# msmobilshield.net
KiCad netlist of a schematic drawn in EAGLE
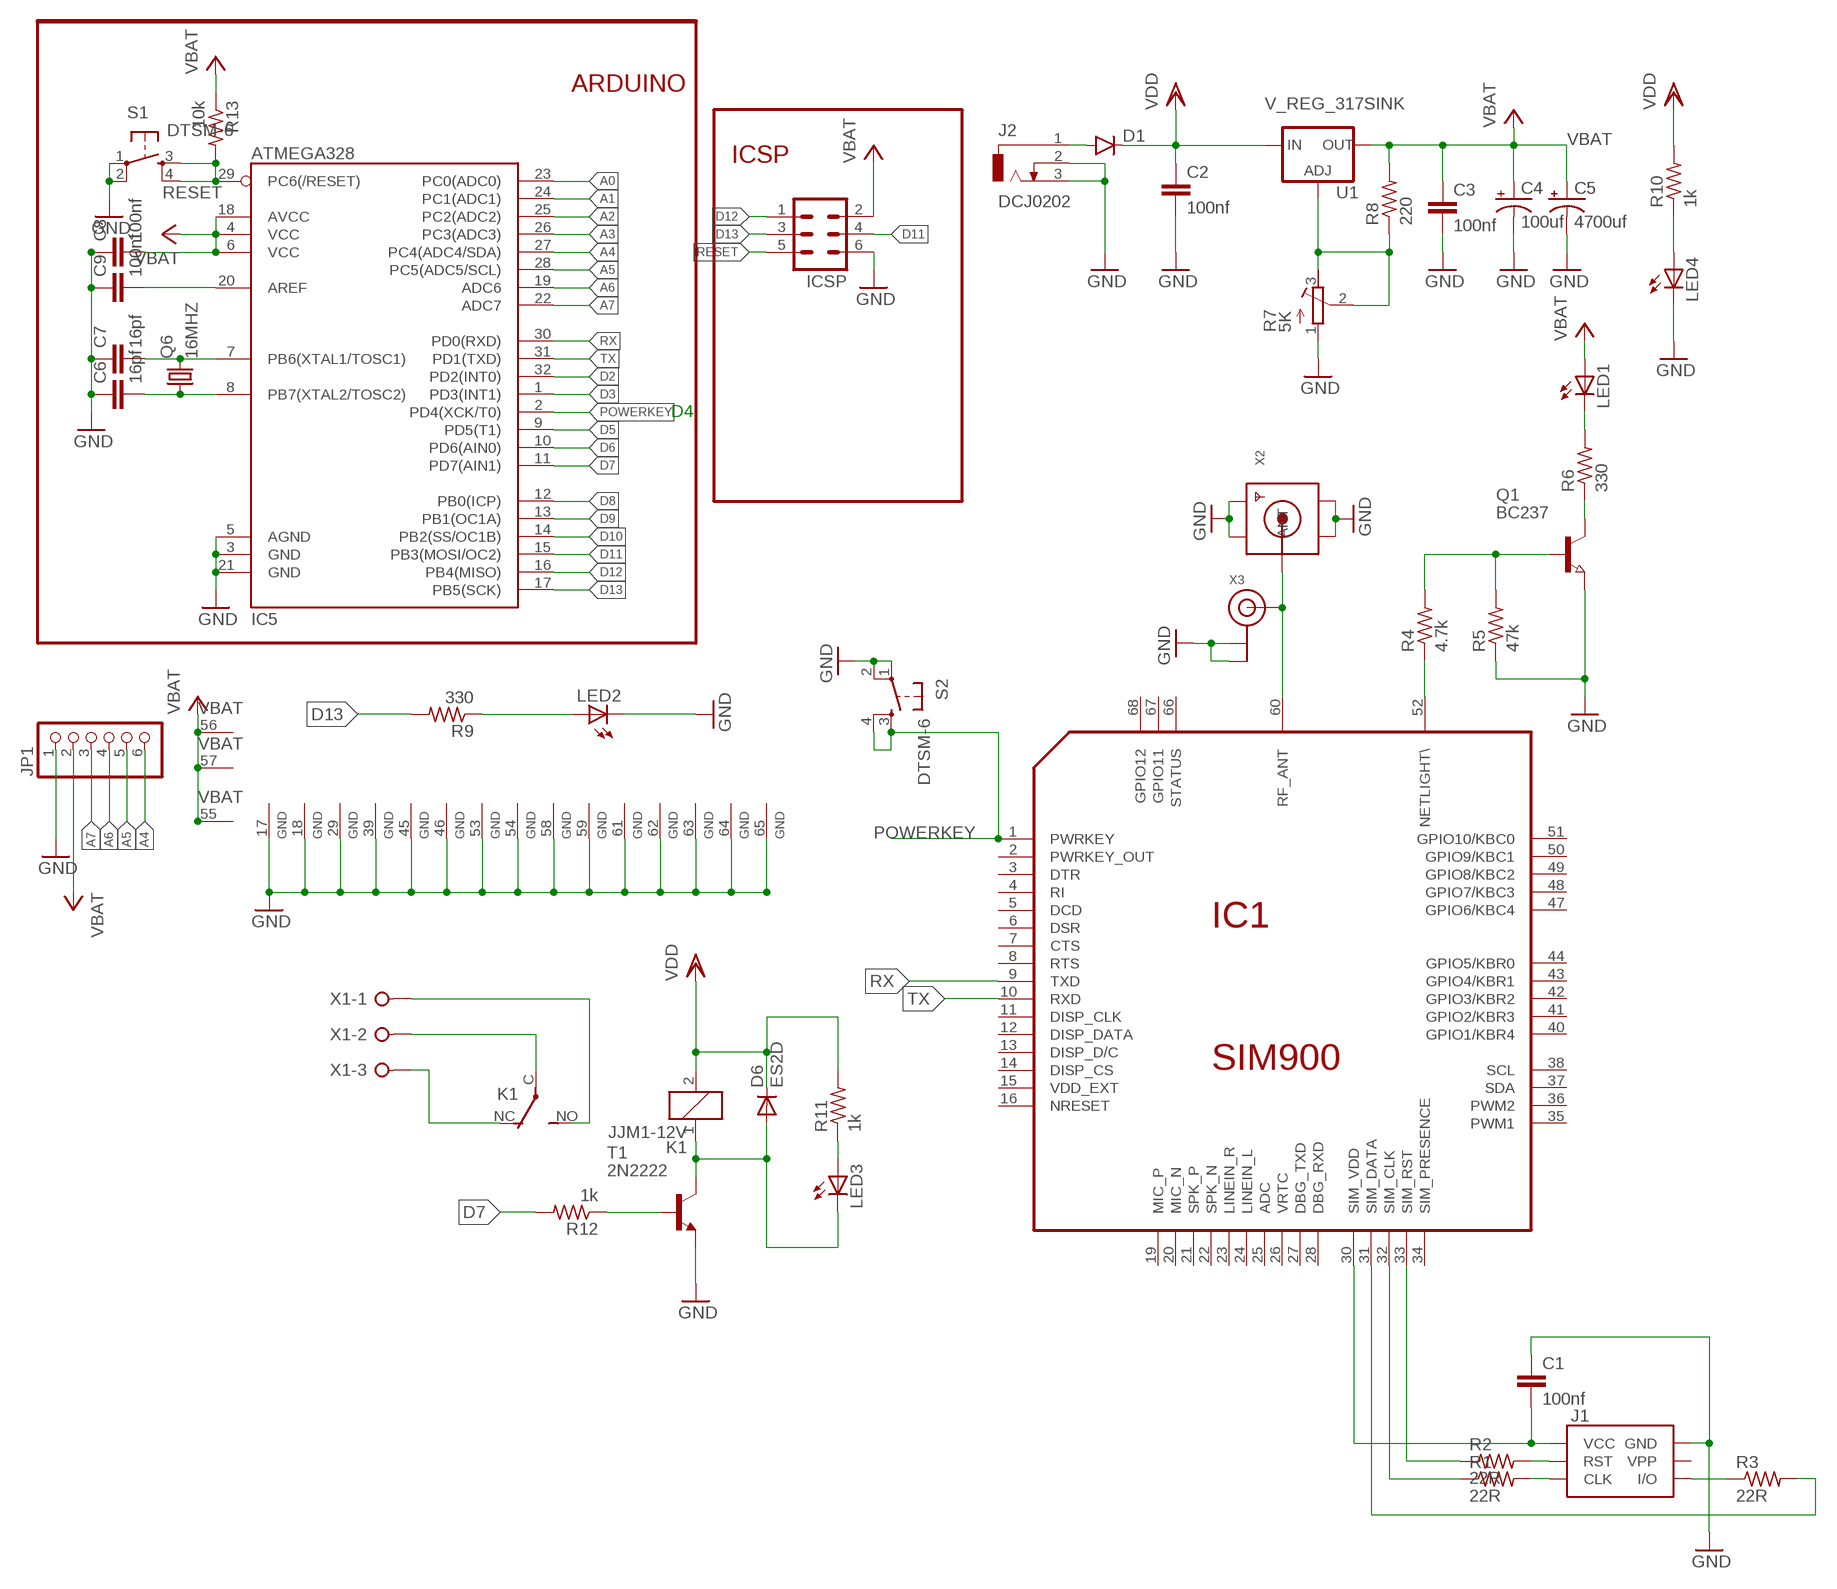
[diagram p0: schematic, sheet 1]

(export (version "E")
  (design (tool "Eeschema 10.0.6"))
  (components
    (comp (ref "C1")
      (value "100nf")
      (footprint "eagle-import:C0805")
      (libsource (lib "eagle-import") (part "C-EUC0805"))
    )
    (comp (ref "C2")
      (value "100nf")
      (footprint "eagle-import:C0805")
      (libsource (lib "eagle-import") (part "C-EUC0805"))
    )
    (comp (ref "C3")
      (value "100nf")
      (footprint "eagle-import:C0805")
      (libsource (lib "eagle-import") (part "C-EUC0805"))
    )
    (comp (ref "C4")
      (value "100uf")
      (footprint "eagle-import:CPOL-RADIAL-100UF-25V")
      (libsource (lib "eagle-import") (part "100UF-25V-20%(PTH)"))
    )
    (comp (ref "C5")
      (value "4700uf")
      (footprint "eagle-import:CPOL-RADIAL-1000UF-25V")
      (libsource (lib "eagle-import") (part "1000UF-25V(PTH)"))
    )
    (comp (ref "C6")
      (value "16pf")
      (footprint "eagle-import:C0805")
      (libsource (lib "eagle-import") (part "C-EUC0805"))
    )
    (comp (ref "C7")
      (value "16pf")
      (footprint "eagle-import:C0805")
      (libsource (lib "eagle-import") (part "C-EUC0805"))
    )
    (comp (ref "C8")
      (value "100nf")
      (footprint "eagle-import:C0805")
      (libsource (lib "eagle-import") (part "C-EUC0805"))
    )
    (comp (ref "C9")
      (value "100nf")
      (footprint "eagle-import:C0805")
      (libsource (lib "eagle-import") (part "C-EUC0805"))
    )
    (comp (ref "D1")
      (value "DIODESMA")
      (footprint "eagle-import:SMA-DIODE")
      (libsource (lib "eagle-import") (part "DIODESMA"))
    )
    (comp (ref "D6")
      (value "ES2D")
      (footprint "eagle-import:SMB")
      (libsource (lib "eagle-import") (part "ES2D"))
    )
    (comp (ref "IC1")
      (value "SIM900")
      (footprint "eagle-import:SIM900")
      (libsource (lib "eagle-import") (part "SIM900"))
    )
    (comp (ref "IC5")
      (value "ATMEGA328")
      (footprint "eagle-import:TQFP32-08")
      (libsource (lib "eagle-import") (part "ATMEGA168"))
    )
    (comp (ref "ICSP")
      (value "ML6")
      (footprint "eagle-import:ML6")
      (libsource (lib "eagle-import") (part "ML6"))
    )
    (comp (ref "J1")
      (value "SIMHOLDERSIM")
      (footprint "eagle-import:SIMHOLDER")
      (libsource (lib "eagle-import") (part "SIMHOLDERSIM"))
    )
    (comp (ref "J2")
      (value "DCJ0202")
      (footprint "eagle-import:DCJ0202")
      (libsource (lib "eagle-import") (part "DCJ0202"))
    )
    (comp (ref "JP1")
      (value "PINHD-1X6")
      (footprint "eagle-import:1X06")
      (libsource (lib "eagle-import") (part "PINHD-1X6"))
    )
    (comp (ref "K1")
      (value "JJM1-12V")
      (footprint "eagle-import:JJM1C")
      (fields (field (name "MF") "AROMAT/ MATSUSHITA"))
      (libsource (lib "eagle-import") (part "JJM1-12V"))
    )
    (comp (ref "LED1")
      (value "LEDCHIPLED_0805")
      (footprint "eagle-import:CHIPLED_0805")
      (libsource (lib "eagle-import") (part "LEDCHIPLED_0805"))
    )
    (comp (ref "LED2")
      (value "LEDCHIPLED_0805")
      (footprint "eagle-import:CHIPLED_0805")
      (libsource (lib "eagle-import") (part "LEDCHIPLED_0805"))
    )
    (comp (ref "LED3")
      (value "LEDCHIPLED_0805")
      (footprint "eagle-import:CHIPLED_0805")
      (libsource (lib "eagle-import") (part "LEDCHIPLED_0805"))
    )
    (comp (ref "LED4")
      (value "LEDCHIPLED_0805")
      (footprint "eagle-import:CHIPLED_0805")
      (libsource (lib "eagle-import") (part "LEDCHIPLED_0805"))
    )
    (comp (ref "Q1")
      (value "BC237")
      (footprint "eagle-import:SOT23")
      (libsource (lib "eagle-import") (part "NPN-TRANSISTOR_SOT23"))
    )
    (comp (ref "Q6")
      (value "16MHZ")
      (footprint "eagle-import:HC49_S")
      (libsource (lib "eagle-import") (part "CRYSTALHC49S"))
    )
    (comp (ref "R1")
      (value "22R")
      (footprint "eagle-import:R0805")
      (libsource (lib "eagle-import") (part "R-US_R0805"))
    )
    (comp (ref "R2")
      (value "22R")
      (footprint "eagle-import:R0805")
      (libsource (lib "eagle-import") (part "R-US_R0805"))
    )
    (comp (ref "R3")
      (value "22R")
      (footprint "eagle-import:R0805")
      (libsource (lib "eagle-import") (part "R-US_R0805"))
    )
    (comp (ref "R4")
      (value "4.7k")
      (footprint "eagle-import:R0805")
      (libsource (lib "eagle-import") (part "R-US_R0805"))
    )
    (comp (ref "R5")
      (value "47k")
      (footprint "eagle-import:R0805")
      (libsource (lib "eagle-import") (part "R-US_R0805"))
    )
    (comp (ref "R6")
      (value "330")
      (footprint "eagle-import:R0805")
      (libsource (lib "eagle-import") (part "R-US_R0805"))
    )
    (comp (ref "R7")
      (value "5K")
      (footprint "eagle-import:RTRIM3103")
      (libsource (lib "eagle-import") (part "R-TRIMM3103"))
    )
    (comp (ref "R8")
      (value "220")
      (footprint "eagle-import:R0805")
      (libsource (lib "eagle-import") (part "R-US_R0805"))
    )
    (comp (ref "R9")
      (value "330")
      (footprint "eagle-import:R0805")
      (libsource (lib "eagle-import") (part "R-US_R0805"))
    )
    (comp (ref "R10")
      (value "1k")
      (footprint "eagle-import:R0805")
      (libsource (lib "eagle-import") (part "R-US_R0805"))
    )
    (comp (ref "R11")
      (value "1k")
      (footprint "eagle-import:R0805")
      (libsource (lib "eagle-import") (part "R-US_R0805"))
    )
    (comp (ref "R12")
      (value "1k")
      (footprint "eagle-import:R0805")
      (libsource (lib "eagle-import") (part "R-US_R0805"))
    )
    (comp (ref "R13")
      (value "10k")
      (footprint "eagle-import:R0805")
      (libsource (lib "eagle-import") (part "R-US_R0805"))
    )
    (comp (ref "S1")
      (value "DTSM-6")
      (footprint "eagle-import:DTSM-6")
      (libsource (lib "eagle-import") (part "DTSM-6"))
    )
    (comp (ref "S2")
      (value "DTSM-6")
      (footprint "eagle-import:DTSM-6")
      (libsource (lib "eagle-import") (part "DTSM-6"))
    )
    (comp (ref "T1")
      (value "2N2222")
      (footprint "eagle-import:SOT23-BEC")
      (libsource (lib "eagle-import") (part "-NPN-SOT23-BECMMBT2222ALT1"))
    )
    (comp (ref "U1")
      (value "V_REG_317SINK")
      (footprint "eagle-import:TO220-ADJ")
      (libsource (lib "eagle-import") (part "V_REG_317SINK"))
    )
    (comp (ref "X1")
      (value "W237-3E")
      (footprint "eagle-import:W237-3E")
      (libsource (lib "eagle-import") (part "W237-3E"))
    )
    (comp (ref "X2")
      (value "SMACONNECTOR")
      (footprint "eagle-import:SMA90_DIP")
      (libsource (lib "eagle-import") (part "SMACONNECTOR"))
    )
    (comp (ref "X3")
      (value "ANTENNA_U.FL")
      (footprint "eagle-import:U.FL")
      (libsource (lib "eagle-import") (part "ANTENNA_U.FL"))
    )
  )
  (nets
    (net (code "1") (name "A0") (class "Default")
      (node (ref "IC5") (pin "23") (pinfunction "PC0(ADC0)_23") (pintype "bidirectional"))
    )
    (net (code "2") (name "A1") (class "Default")
      (node (ref "IC5") (pin "24") (pinfunction "PC1(ADC1)_24") (pintype "bidirectional"))
    )
    (net (code "3") (name "A2") (class "Default")
      (node (ref "IC5") (pin "25") (pinfunction "PC2(ADC2)_25") (pintype "bidirectional"))
    )
    (net (code "4") (name "A3") (class "Default")
      (node (ref "IC5") (pin "26") (pinfunction "PC3(ADC3)_26") (pintype "bidirectional"))
    )
    (net (code "5") (name "A4") (class "Default")
      (node (ref "IC5") (pin "27") (pinfunction "PC4(ADC4/SDA)_27") (pintype "bidirectional"))
      (node (ref "JP1") (pin "6") (pinfunction "6_6") (pintype "passive"))
    )
    (net (code "6") (name "A5") (class "Default")
      (node (ref "IC5") (pin "28") (pinfunction "PC5(ADC5/SCL)_28") (pintype "bidirectional"))
      (node (ref "JP1") (pin "5") (pinfunction "5_5") (pintype "passive"))
    )
    (net (code "7") (name "A6") (class "Default")
      (node (ref "IC5") (pin "19") (pinfunction "ADC6_19") (pintype "bidirectional"))
      (node (ref "JP1") (pin "4") (pinfunction "4_4") (pintype "passive"))
    )
    (net (code "8") (name "A7") (class "Default")
      (node (ref "IC5") (pin "22") (pinfunction "ADC7_22") (pintype "bidirectional"))
      (node (ref "JP1") (pin "3") (pinfunction "3_3") (pintype "passive"))
    )
    (net (code "9") (name "D2") (class "Default")
      (node (ref "IC5") (pin "32") (pinfunction "PD2(INT0)_32") (pintype "bidirectional"))
    )
    (net (code "10") (name "D3") (class "Default")
      (node (ref "IC5") (pin "1") (pinfunction "PD3(INT1)_1") (pintype "bidirectional"))
    )
    (net (code "11") (name "D5") (class "Default")
      (node (ref "IC5") (pin "9") (pinfunction "PD5(T1)_9") (pintype "bidirectional"))
    )
    (net (code "12") (name "D6") (class "Default")
      (node (ref "IC5") (pin "10") (pinfunction "PD6(AIN0)_10") (pintype "bidirectional"))
    )
    (net (code "13") (name "D7") (class "Default")
      (node (ref "IC5") (pin "11") (pinfunction "PD7(AIN1)_11") (pintype "bidirectional"))
      (node (ref "R12") (pin "2") (pinfunction "2_2") (pintype "passive"))
    )
    (net (code "14") (name "D8") (class "Default")
      (node (ref "IC5") (pin "12") (pinfunction "PB0(ICP)_12") (pintype "bidirectional"))
    )
    (net (code "15") (name "D9") (class "Default")
      (node (ref "IC5") (pin "13") (pinfunction "PB1(OC1A)_13") (pintype "bidirectional"))
    )
    (net (code "16") (name "D10") (class "Default")
      (node (ref "IC5") (pin "14") (pinfunction "PB2(SS/OC1B)_14") (pintype "bidirectional"))
    )
    (net (code "17") (name "D11") (class "Default")
      (node (ref "IC5") (pin "15") (pinfunction "PB3(MOSI/OC2)_15") (pintype "bidirectional"))
      (node (ref "ICSP") (pin "4") (pinfunction "4_4") (pintype "passive"))
    )
    (net (code "18") (name "D12") (class "Default")
      (node (ref "IC5") (pin "16") (pinfunction "PB4(MISO)_16") (pintype "bidirectional"))
      (node (ref "ICSP") (pin "1") (pinfunction "1_1") (pintype "passive"))
    )
    (net (code "19") (name "D13") (class "Default")
      (node (ref "IC5") (pin "17") (pinfunction "PB5(SCK)_17") (pintype "bidirectional"))
      (node (ref "ICSP") (pin "3") (pinfunction "3_3") (pintype "passive"))
      (node (ref "R9") (pin "2") (pinfunction "2_2") (pintype "passive"))
    )
    (net (code "20") (name "GND") (class "Default")
      (node (ref "C1") (pin "1") (pinfunction "1_1") (pintype "passive"))
      (node (ref "C2") (pin "2") (pinfunction "2_2") (pintype "passive"))
      (node (ref "C3") (pin "2") (pinfunction "2_2") (pintype "passive"))
      (node (ref "C4") (pin "2") (pinfunction "-_2") (pintype "passive"))
      (node (ref "C5") (pin "-") (pinfunction "-_-") (pintype "passive"))
      (node (ref "C6") (pin "1") (pinfunction "1_1") (pintype "passive"))
      (node (ref "C7") (pin "1") (pinfunction "1_1") (pintype "passive"))
      (node (ref "C8") (pin "1") (pinfunction "1_1") (pintype "passive"))
      (node (ref "C9") (pin "1") (pinfunction "1_1") (pintype "passive"))
      (node (ref "IC1") (pin "17") (pinfunction "GND_17") (pintype "power_in"))
      (node (ref "IC1") (pin "18") (pinfunction "GND_18") (pintype "power_in"))
      (node (ref "IC1") (pin "29") (pinfunction "GND_29") (pintype "power_in"))
      (node (ref "IC1") (pin "39") (pinfunction "GND_39") (pintype "power_in"))
      (node (ref "IC1") (pin "45") (pinfunction "GND_45") (pintype "power_in"))
      (node (ref "IC1") (pin "46") (pinfunction "GND_46") (pintype "power_in"))
      (node (ref "IC1") (pin "53") (pinfunction "GND_53") (pintype "power_in"))
      (node (ref "IC1") (pin "54") (pinfunction "GND_54") (pintype "power_in"))
      (node (ref "IC1") (pin "58") (pinfunction "GND_58") (pintype "power_in"))
      (node (ref "IC1") (pin "59") (pinfunction "GND_59") (pintype "power_in"))
      (node (ref "IC1") (pin "61") (pinfunction "GND_61") (pintype "power_in"))
      (node (ref "IC1") (pin "62") (pinfunction "GND_62") (pintype "power_in"))
      (node (ref "IC1") (pin "63") (pinfunction "GND_63") (pintype "power_in"))
      (node (ref "IC1") (pin "64") (pinfunction "GND_64") (pintype "power_in"))
      (node (ref "IC1") (pin "65") (pinfunction "GND_65") (pintype "power_in"))
      (node (ref "IC5") (pin "21") (pinfunction "GND_21") (pintype "bidirectional"))
      (node (ref "IC5") (pin "3") (pinfunction "GND_3") (pintype "bidirectional"))
      (node (ref "IC5") (pin "5") (pinfunction "AGND_5") (pintype "bidirectional"))
      (node (ref "ICSP") (pin "6") (pinfunction "6_6") (pintype "passive"))
      (node (ref "J1") (pin "C5") (pinfunction "GND_C5") (pintype "power_in"))
      (node (ref "J2") (pin "2") (pinfunction "2_2") (pintype "passive"))
      (node (ref "J2") (pin "3") (pinfunction "3_3") (pintype "passive"))
      (node (ref "JP1") (pin "1") (pinfunction "1_1") (pintype "passive"))
      (node (ref "LED2") (pin "C") (pinfunction "C_C") (pintype "passive"))
      (node (ref "LED4") (pin "C") (pinfunction "C_C") (pintype "passive"))
      (node (ref "Q1") (pin "2") (pinfunction "E_2") (pintype "passive"))
      (node (ref "R5") (pin "1") (pinfunction "1_1") (pintype "passive"))
      (node (ref "R7") (pin "1") (pinfunction "A_1") (pintype "passive"))
      (node (ref "S1") (pin "1") (pinfunction "1_1") (pintype "passive"))
      (node (ref "S1") (pin "2") (pinfunction "2_2") (pintype "passive"))
      (node (ref "S2") (pin "1") (pinfunction "1_1") (pintype "passive"))
      (node (ref "S2") (pin "2") (pinfunction "2_2") (pintype "passive"))
      (node (ref "T1") (pin "E") (pinfunction "E_E") (pintype "passive"))
      (node (ref "X2") (pin "GND1") (pinfunction "GND1_GND1") (pintype "power_in"))
      (node (ref "X2") (pin "GND2") (pinfunction "GND2_GND2") (pintype "power_in"))
      (node (ref "X2") (pin "GND3") (pinfunction "GND3_GND3") (pintype "power_in"))
      (node (ref "X2") (pin "GND4") (pinfunction "GND4_GND4") (pintype "power_in"))
      (node (ref "X3") (pin "1") (pinfunction "GND_1") (pintype "passive"))
      (node (ref "X3") (pin "2") (pinfunction "GND_2") (pintype "passive"))
    )
    (net (code "21") (name "Net-(D1-PadA)") (class "Default")
      (node (ref "D1") (pin "A") (pinfunction "A_A") (pintype "passive"))
      (node (ref "J2") (pin "1") (pinfunction "1_1") (pintype "passive"))
    )
    (net (code "22") (name "Net-(D6-PadA)") (class "Default")
      (node (ref "D6") (pin "A") (pinfunction "A_A") (pintype "passive"))
      (node (ref "K1") (pin "1") (pinfunction "1_1") (pintype "passive"))
      (node (ref "LED3") (pin "C") (pinfunction "C_C") (pintype "passive"))
      (node (ref "T1") (pin "C") (pinfunction "C_C") (pintype "passive"))
    )
    (net (code "23") (name "Net-(IC1A-NETLIGHT\\)") (class "Default")
      (node (ref "IC1") (pin "52") (pinfunction "NETLIGHT\\_52") (pintype "bidirectional"))
      (node (ref "R4") (pin "1") (pinfunction "1_1") (pintype "passive"))
    )
    (net (code "24") (name "Net-(IC1A-RF_ANT)") (class "Default")
      (node (ref "IC1") (pin "60") (pinfunction "RF_ANT_60") (pintype "bidirectional"))
      (node (ref "X2") (pin "ANTENNA") (pinfunction "ANT_ANTENNA") (pintype "bidirectional"))
      (node (ref "X3") (pin "3") (pinfunction "SIGNAL_3") (pintype "passive"))
    )
    (net (code "25") (name "Net-(IC1A-SIM_CLK)") (class "Default")
      (node (ref "IC1") (pin "32") (pinfunction "SIM_CLK_32") (pintype "bidirectional"))
      (node (ref "R1") (pin "1") (pinfunction "1_1") (pintype "passive"))
    )
    (net (code "26") (name "Net-(IC1A-SIM_DATA)") (class "Default")
      (node (ref "IC1") (pin "31") (pinfunction "SIM_DATA_31") (pintype "bidirectional"))
      (node (ref "R3") (pin "2") (pinfunction "2_2") (pintype "passive"))
    )
    (net (code "27") (name "Net-(IC1A-SIM_RST)") (class "Default")
      (node (ref "IC1") (pin "33") (pinfunction "SIM_RST_33") (pintype "bidirectional"))
      (node (ref "R2") (pin "1") (pinfunction "1_1") (pintype "passive"))
    )
    (net (code "28") (name "Net-(IC1A-SIM_VDD)") (class "Default")
      (node (ref "C1") (pin "2") (pinfunction "2_2") (pintype "passive"))
      (node (ref "IC1") (pin "30") (pinfunction "SIM_VDD_30") (pintype "bidirectional"))
      (node (ref "J1") (pin "C1") (pinfunction "VCC_C1") (pintype "power_in"))
    )
    (net (code "29") (name "Net-(IC5-AREF)") (class "Default")
      (node (ref "C9") (pin "2") (pinfunction "2_2") (pintype "passive"))
      (node (ref "IC5") (pin "20") (pinfunction "AREF_20") (pintype "bidirectional"))
    )
    (net (code "30") (name "Net-(IC5-PB6(XTAL1{slash}TOSC1))") (class "Default")
      (node (ref "C7") (pin "2") (pinfunction "2_2") (pintype "passive"))
      (node (ref "IC5") (pin "7") (pinfunction "PB6(XTAL1/TOSC1)_7") (pintype "bidirectional"))
      (node (ref "Q6") (pin "2") (pinfunction "2_2") (pintype "passive"))
    )
    (net (code "31") (name "Net-(IC5-PB7(XTAL2{slash}TOSC2))") (class "Default")
      (node (ref "C6") (pin "2") (pinfunction "2_2") (pintype "passive"))
      (node (ref "IC5") (pin "8") (pinfunction "PB7(XTAL2/TOSC2)_8") (pintype "bidirectional"))
      (node (ref "Q6") (pin "1") (pinfunction "1_1") (pintype "passive"))
    )
    (net (code "32") (name "Net-(J1-CLK)") (class "Default")
      (node (ref "J1") (pin "C3") (pinfunction "CLK_C3") (pintype "input"))
      (node (ref "R1") (pin "2") (pinfunction "2_2") (pintype "passive"))
    )
    (net (code "33") (name "Net-(J1-I{slash}O)") (class "Default")
      (node (ref "J1") (pin "C7") (pinfunction "I/O_C7") (pintype "bidirectional"))
      (node (ref "R3") (pin "1") (pinfunction "1_1") (pintype "passive"))
    )
    (net (code "34") (name "Net-(J1-RST)") (class "Default")
      (node (ref "J1") (pin "C2") (pinfunction "RST_C2") (pintype "input"))
      (node (ref "R2") (pin "2") (pinfunction "2_2") (pintype "passive"))
    )
    (net (code "35") (name "Net-(K1B-O)") (class "Default")
      (node (ref "K1") (pin "NC") (pinfunction "O_NC") (pintype "passive"))
      (node (ref "X1") (pin "3") (pinfunction "KL_3") (pintype "passive"))
    )
    (net (code "36") (name "Net-(K1B-P)") (class "Default")
      (node (ref "K1") (pin "C") (pinfunction "P_C") (pintype "passive"))
      (node (ref "X1") (pin "2") (pinfunction "KL_2") (pintype "passive"))
    )
    (net (code "37") (name "Net-(K1B-S)") (class "Default")
      (node (ref "K1") (pin "NO") (pinfunction "S_NO") (pintype "passive"))
      (node (ref "X1") (pin "1") (pinfunction "KL_1") (pintype "passive"))
    )
    (net (code "38") (name "Net-(LED1-PadC)") (class "Default")
      (node (ref "LED1") (pin "C") (pinfunction "C_C") (pintype "passive"))
      (node (ref "R6") (pin "2") (pinfunction "2_2") (pintype "passive"))
    )
    (net (code "39") (name "Net-(LED2-PadA)") (class "Default")
      (node (ref "LED2") (pin "A") (pinfunction "A_A") (pintype "passive"))
      (node (ref "R9") (pin "1") (pinfunction "1_1") (pintype "passive"))
    )
    (net (code "40") (name "Net-(LED3-PadA)") (class "Default")
      (node (ref "LED3") (pin "A") (pinfunction "A_A") (pintype "passive"))
      (node (ref "R11") (pin "1") (pinfunction "1_1") (pintype "passive"))
    )
    (net (code "41") (name "Net-(LED4-PadA)") (class "Default")
      (node (ref "LED4") (pin "A") (pinfunction "A_A") (pintype "passive"))
      (node (ref "R10") (pin "1") (pinfunction "1_1") (pintype "passive"))
    )
    (net (code "42") (name "Net-(Q1-B)") (class "Default")
      (node (ref "Q1") (pin "1") (pinfunction "B_1") (pintype "passive"))
      (node (ref "R4") (pin "2") (pinfunction "2_2") (pintype "passive"))
      (node (ref "R5") (pin "2") (pinfunction "2_2") (pintype "passive"))
    )
    (net (code "43") (name "Net-(Q1-C)") (class "Default")
      (node (ref "Q1") (pin "3") (pinfunction "C_3") (pintype "passive"))
      (node (ref "R6") (pin "1") (pinfunction "1_1") (pintype "passive"))
    )
    (net (code "44") (name "Net-(R7-E)") (class "Default")
      (node (ref "R7") (pin "2") (pinfunction "S_2") (pintype "passive"))
      (node (ref "R7") (pin "3") (pinfunction "E_3") (pintype "passive"))
      (node (ref "R8") (pin "1") (pinfunction "1_1") (pintype "passive"))
      (node (ref "U1") (pin "ADJ") (pinfunction "ADJ_ADJ") (pintype "input"))
    )
    (net (code "45") (name "Net-(R12-Pad1)") (class "Default")
      (node (ref "R12") (pin "1") (pinfunction "1_1") (pintype "passive"))
      (node (ref "T1") (pin "B") (pinfunction "B_B") (pintype "passive"))
    )
    (net (code "46") (name "POWERKEY") (class "Default")
      (node (ref "IC1") (pin "1") (pinfunction "PWRKEY_1") (pintype "bidirectional"))
      (node (ref "IC5") (pin "2") (pinfunction "PD4(XCK/T0)_2") (pintype "bidirectional"))
      (node (ref "S2") (pin "3") (pinfunction "3_3") (pintype "passive"))
      (node (ref "S2") (pin "4") (pinfunction "4_4") (pintype "passive"))
    )
    (net (code "47") (name "RESET") (class "Default")
      (node (ref "IC5") (pin "29") (pinfunction "PC6(/RESET)_29") (pintype "bidirectional"))
      (node (ref "ICSP") (pin "5") (pinfunction "5_5") (pintype "passive"))
      (node (ref "R13") (pin "2") (pinfunction "2_2") (pintype "passive"))
      (node (ref "S1") (pin "3") (pinfunction "3_3") (pintype "passive"))
      (node (ref "S1") (pin "4") (pinfunction "4_4") (pintype "passive"))
    )
    (net (code "48") (name "RX") (class "Default")
      (node (ref "IC1") (pin "9") (pinfunction "TXD_9") (pintype "bidirectional"))
      (node (ref "IC5") (pin "30") (pinfunction "PD0(RXD)_30") (pintype "bidirectional"))
    )
    (net (code "49") (name "TX") (class "Default")
      (node (ref "IC1") (pin "10") (pinfunction "RXD_10") (pintype "bidirectional"))
      (node (ref "IC5") (pin "31") (pinfunction "PD1(TXD)_31") (pintype "bidirectional"))
    )
    (net (code "50") (name "VBAT") (class "Default")
      (node (ref "C3") (pin "1") (pinfunction "1_1") (pintype "passive"))
      (node (ref "C4") (pin "1") (pinfunction "+_1") (pintype "passive"))
      (node (ref "C5") (pin "+") (pinfunction "+_+") (pintype "passive"))
      (node (ref "C8") (pin "2") (pinfunction "2_2") (pintype "passive"))
      (node (ref "IC1") (pin "55") (pinfunction "VBAT_55") (pintype "power_in"))
      (node (ref "IC1") (pin "56") (pinfunction "VBAT_56") (pintype "power_in"))
      (node (ref "IC1") (pin "57") (pinfunction "VBAT_57") (pintype "power_in"))
      (node (ref "IC5") (pin "18") (pinfunction "AVCC_18") (pintype "bidirectional"))
      (node (ref "IC5") (pin "4") (pinfunction "VCC_4") (pintype "bidirectional"))
      (node (ref "IC5") (pin "6") (pinfunction "VCC_6") (pintype "bidirectional"))
      (node (ref "ICSP") (pin "2") (pinfunction "2_2") (pintype "passive"))
      (node (ref "JP1") (pin "2") (pinfunction "2_2") (pintype "passive"))
      (node (ref "LED1") (pin "A") (pinfunction "A_A") (pintype "passive"))
      (node (ref "R13") (pin "1") (pinfunction "1_1") (pintype "passive"))
      (node (ref "R8") (pin "2") (pinfunction "2_2") (pintype "passive"))
      (node (ref "U1") (pin "OUT") (pinfunction "OUT_OUT") (pintype "output"))
    )
    (net (code "51") (name "VDD") (class "Default")
      (node (ref "C2") (pin "1") (pinfunction "1_1") (pintype "passive"))
      (node (ref "D1") (pin "C") (pinfunction "C_C") (pintype "passive"))
      (node (ref "D6") (pin "C") (pinfunction "C_C") (pintype "passive"))
      (node (ref "K1") (pin "2") (pinfunction "2_2") (pintype "passive"))
      (node (ref "R10") (pin "2") (pinfunction "2_2") (pintype "passive"))
      (node (ref "R11") (pin "2") (pinfunction "2_2") (pintype "passive"))
      (node (ref "U1") (pin "IN") (pinfunction "IN_IN") (pintype "input"))
    )
    (net (code "52") (name "unconnected-(IC1A-ADC-Pad25)") (class "Default")
      (node (ref "IC1") (pin "25") (pinfunction "ADC_25") (pintype "bidirectional"))
    )
    (net (code "53") (name "unconnected-(IC1A-CTS-Pad7)") (class "Default")
      (node (ref "IC1") (pin "7") (pinfunction "CTS_7") (pintype "bidirectional"))
    )
    (net (code "54") (name "unconnected-(IC1A-DBG_RXD-Pad28)") (class "Default")
      (node (ref "IC1") (pin "28") (pinfunction "DBG_RXD_28") (pintype "bidirectional"))
    )
    (net (code "55") (name "unconnected-(IC1A-DBG_TXD-Pad27)") (class "Default")
      (node (ref "IC1") (pin "27") (pinfunction "DBG_TXD_27") (pintype "bidirectional"))
    )
    (net (code "56") (name "unconnected-(IC1A-DCD-Pad5)") (class "Default")
      (node (ref "IC1") (pin "5") (pinfunction "DCD_5") (pintype "bidirectional"))
    )
    (net (code "57") (name "unconnected-(IC1A-DISP_CLK-Pad11)") (class "Default")
      (node (ref "IC1") (pin "11") (pinfunction "DISP_CLK_11") (pintype "bidirectional"))
    )
    (net (code "58") (name "unconnected-(IC1A-DISP_CS-Pad14)") (class "Default")
      (node (ref "IC1") (pin "14") (pinfunction "DISP_CS_14") (pintype "bidirectional"))
    )
    (net (code "59") (name "unconnected-(IC1A-DISP_DATA-Pad12)") (class "Default")
      (node (ref "IC1") (pin "12") (pinfunction "DISP_DATA_12") (pintype "bidirectional"))
    )
    (net (code "60") (name "unconnected-(IC1A-DISP_D{slash}C-Pad13)") (class "Default")
      (node (ref "IC1") (pin "13") (pinfunction "DISP_D/C_13") (pintype "bidirectional"))
    )
    (net (code "61") (name "unconnected-(IC1A-DSR-Pad6)") (class "Default")
      (node (ref "IC1") (pin "6") (pinfunction "DSR_6") (pintype "bidirectional"))
    )
    (net (code "62") (name "unconnected-(IC1A-DTR-Pad3)") (class "Default")
      (node (ref "IC1") (pin "3") (pinfunction "DTR_3") (pintype "bidirectional"))
    )
    (net (code "63") (name "unconnected-(IC1A-GPIO1{slash}KBR4-Pad40)") (class "Default")
      (node (ref "IC1") (pin "40") (pinfunction "GPIO1/KBR4_40") (pintype "bidirectional"))
    )
    (net (code "64") (name "unconnected-(IC1A-GPIO2{slash}KBR3-Pad41)") (class "Default")
      (node (ref "IC1") (pin "41") (pinfunction "GPIO2/KBR3_41") (pintype "bidirectional"))
    )
    (net (code "65") (name "unconnected-(IC1A-GPIO3{slash}KBR2-Pad42)") (class "Default")
      (node (ref "IC1") (pin "42") (pinfunction "GPIO3/KBR2_42") (pintype "bidirectional"))
    )
    (net (code "66") (name "unconnected-(IC1A-GPIO4{slash}KBR1-Pad43)") (class "Default")
      (node (ref "IC1") (pin "43") (pinfunction "GPIO4/KBR1_43") (pintype "bidirectional"))
    )
    (net (code "67") (name "unconnected-(IC1A-GPIO5{slash}KBR0-Pad44)") (class "Default")
      (node (ref "IC1") (pin "44") (pinfunction "GPIO5/KBR0_44") (pintype "bidirectional"))
    )
    (net (code "68") (name "unconnected-(IC1A-GPIO6{slash}KBC4-Pad47)") (class "Default")
      (node (ref "IC1") (pin "47") (pinfunction "GPIO6/KBC4_47") (pintype "bidirectional"))
    )
    (net (code "69") (name "unconnected-(IC1A-GPIO7{slash}KBC3-Pad48)") (class "Default")
      (node (ref "IC1") (pin "48") (pinfunction "GPIO7/KBC3_48") (pintype "bidirectional"))
    )
    (net (code "70") (name "unconnected-(IC1A-GPIO8{slash}KBC2-Pad49)") (class "Default")
      (node (ref "IC1") (pin "49") (pinfunction "GPIO8/KBC2_49") (pintype "bidirectional"))
    )
    (net (code "71") (name "unconnected-(IC1A-GPIO9{slash}KBC1-Pad50)") (class "Default")
      (node (ref "IC1") (pin "50") (pinfunction "GPIO9/KBC1_50") (pintype "bidirectional"))
    )
    (net (code "72") (name "unconnected-(IC1A-GPIO10{slash}KBC0-Pad51)") (class "Default")
      (node (ref "IC1") (pin "51") (pinfunction "GPIO10/KBC0_51") (pintype "bidirectional"))
    )
    (net (code "73") (name "unconnected-(IC1A-GPIO11-Pad67)") (class "Default")
      (node (ref "IC1") (pin "67") (pinfunction "GPIO11_67") (pintype "bidirectional"))
    )
    (net (code "74") (name "unconnected-(IC1A-GPIO12-Pad68)") (class "Default")
      (node (ref "IC1") (pin "68") (pinfunction "GPIO12_68") (pintype "bidirectional"))
    )
    (net (code "75") (name "unconnected-(IC1A-LINEIN_L-Pad24)") (class "Default")
      (node (ref "IC1") (pin "24") (pinfunction "LINEIN_L_24") (pintype "bidirectional"))
    )
    (net (code "76") (name "unconnected-(IC1A-LINEIN_R-Pad23)") (class "Default")
      (node (ref "IC1") (pin "23") (pinfunction "LINEIN_R_23") (pintype "bidirectional"))
    )
    (net (code "77") (name "unconnected-(IC1A-MIC_N-Pad20)") (class "Default")
      (node (ref "IC1") (pin "20") (pinfunction "MIC_N_20") (pintype "bidirectional"))
    )
    (net (code "78") (name "unconnected-(IC1A-MIC_P-Pad19)") (class "Default")
      (node (ref "IC1") (pin "19") (pinfunction "MIC_P_19") (pintype "bidirectional"))
    )
    (net (code "79") (name "unconnected-(IC1A-NRESET-Pad16)") (class "Default")
      (node (ref "IC1") (pin "16") (pinfunction "NRESET_16") (pintype "bidirectional"))
    )
    (net (code "80") (name "unconnected-(IC1A-PWM1-Pad35)") (class "Default")
      (node (ref "IC1") (pin "35") (pinfunction "PWM1_35") (pintype "bidirectional"))
    )
    (net (code "81") (name "unconnected-(IC1A-PWM2-Pad36)") (class "Default")
      (node (ref "IC1") (pin "36") (pinfunction "PWM2_36") (pintype "bidirectional"))
    )
    (net (code "82") (name "unconnected-(IC1A-PWRKEY_OUT-Pad2)") (class "Default")
      (node (ref "IC1") (pin "2") (pinfunction "PWRKEY_OUT_2") (pintype "bidirectional"))
    )
    (net (code "83") (name "unconnected-(IC1A-RI-Pad4)") (class "Default")
      (node (ref "IC1") (pin "4") (pinfunction "RI_4") (pintype "bidirectional"))
    )
    (net (code "84") (name "unconnected-(IC1A-RTS-Pad8)") (class "Default")
      (node (ref "IC1") (pin "8") (pinfunction "RTS_8") (pintype "bidirectional"))
    )
    (net (code "85") (name "unconnected-(IC1A-SCL-Pad38)") (class "Default")
      (node (ref "IC1") (pin "38") (pinfunction "SCL_38") (pintype "bidirectional"))
    )
    (net (code "86") (name "unconnected-(IC1A-SDA-Pad37)") (class "Default")
      (node (ref "IC1") (pin "37") (pinfunction "SDA_37") (pintype "bidirectional"))
    )
    (net (code "87") (name "unconnected-(IC1A-SIM_PRESENCE-Pad34)") (class "Default")
      (node (ref "IC1") (pin "34") (pinfunction "SIM_PRESENCE_34") (pintype "bidirectional"))
    )
    (net (code "88") (name "unconnected-(IC1A-SPK_N-Pad22)") (class "Default")
      (node (ref "IC1") (pin "22") (pinfunction "SPK_N_22") (pintype "bidirectional"))
    )
    (net (code "89") (name "unconnected-(IC1A-SPK_P-Pad21)") (class "Default")
      (node (ref "IC1") (pin "21") (pinfunction "SPK_P_21") (pintype "bidirectional"))
    )
    (net (code "90") (name "unconnected-(IC1A-STATUS-Pad66)") (class "Default")
      (node (ref "IC1") (pin "66") (pinfunction "STATUS_66") (pintype "bidirectional"))
    )
    (net (code "91") (name "unconnected-(IC1A-VDD_EXT-Pad15)") (class "Default")
      (node (ref "IC1") (pin "15") (pinfunction "VDD_EXT_15") (pintype "bidirectional"))
    )
    (net (code "92") (name "unconnected-(IC1A-VRTC-Pad26)") (class "Default")
      (node (ref "IC1") (pin "26") (pinfunction "VRTC_26") (pintype "bidirectional"))
    )
    (net (code "93") (name "unconnected-(J1-VPP-PadC6)") (class "Default")
      (node (ref "J1") (pin "C6") (pinfunction "VPP_C6") (pintype "input"))
    )
  )
)
